# Sensors.net
KiCad netlist of a schematic drawn in Altium Designer
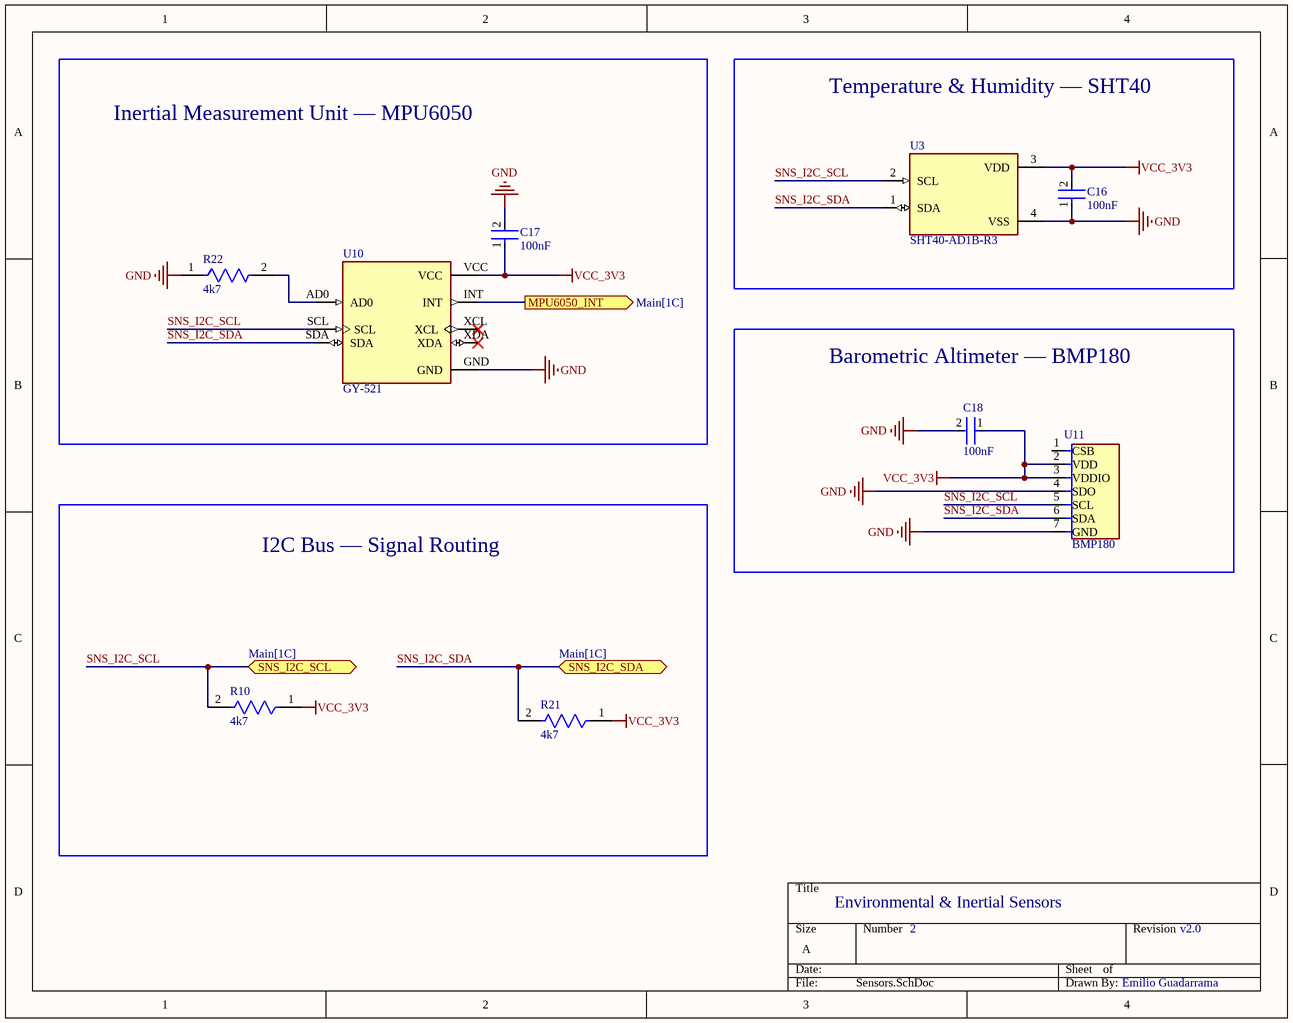
[diagram p0: Sensors.SchDoc]

(export (version "E")
  (design (tool "Eeschema 10.0.6"))
  (components
    (comp (ref "C16")
      (value "100nF")
      (footprint "FP-C0805C-DN-MFG")
      (description "CAP CER 0.1UF 50V X7R 0805")
      (fields
        (field (name "MANUFACTURER PART NUMBER") "C0805C104K5RACTU")
        (field (name "MANUFACTURER") "KEMET")
      )
      (libsource (lib "Altium Content Vault") (part "b4654b650e69147ec39a6b967a45e02"))
    )
    (comp (ref "C17")
      (value "100nF")
      (footprint "FP-C0805C-DN-MFG")
      (description "CAP CER 0.1UF 50V X7R 0805")
      (fields
        (field (name "MANUFACTURER PART NUMBER") "C0805C104K5RACTU")
        (field (name "MANUFACTURER") "KEMET")
      )
      (libsource (lib "Altium Content Vault") (part "b4654b650e69147ec39a6b967a45e02"))
    )
    (comp (ref "C18")
      (value "100nF")
      (footprint "FP-C0805C-DN-MFG")
      (description "CAP CER 0.1UF 50V X7R 0805")
      (fields
        (field (name "MANUFACTURER PART NUMBER") "C0805C104K5RACTU")
        (field (name "MANUFACTURER") "KEMET")
      )
      (libsource (lib "Altium Content Vault") (part "b4654b650e69147ec39a6b967a45e02"))
    )
    (comp (ref "R10")
      (value "4k7")
      (footprint "FP-MCT0603-IPC_A")
      (description "RES SMD 100 OHM 1% 1/8W 0603")
      (fields (field (name "TOLERANCE") "0.1%"))
      (libsource (lib "Altium Content Vault") (part "1029c3af85768c4190bb7ad29bc67b5"))
    )
    (comp (ref "R21")
      (value "4k7")
      (footprint "FP-MCT0603-IPC_A")
      (description "RES SMD 100 OHM 1% 1/8W 0603")
      (fields (field (name "TOLERANCE") "0.1%"))
      (libsource (lib "Altium Content Vault") (part "1029c3af85768c4190bb7ad29bc67b5"))
    )
    (comp (ref "R22")
      (value "4k7")
      (footprint "FP-MCT0603-IPC_A")
      (description "RES SMD 100 OHM 1% 1/8W 0603")
      (fields (field (name "TOLERANCE") "0.1%"))
      (libsource (lib "Altium Content Vault") (part "1029c3af85768c4190bb7ad29bc67b5"))
    )
    (comp (ref "U3")
      (value "SHT40-AD1B-R3")
      (footprint "SHT4X")
      (fields (field (name "MF") "Sensirion"))
      (libsource (lib "HumTemp-SHT40-AD1B-R3") (part "SHT40-AD1B-R3"))
    )
    (comp (ref "U10")
      (value "GY-521")
      (footprint "MODULE_GY-521")
      (description "Triple Axis Accelerometer Gyro Breakout")
      (fields (field (name "MF") "GODREAM FORDREAM CO., LIMITED"))
      (libsource (lib "GY-521_IMU_with_MountingHoles") (part "GY-521"))
    )
    (comp (ref "U11")
      (value "BMP180")
      (footprint "LGA7-1.5-3.8X3.6MM")
      (description "Pressure Sensor 4.35PSI ~ 15.95PSI (30kPa ~ 110kPa) Absolute - 16 ~ 19 b 7-VLGA")
      (fields (field (name "MF") "Bosch"))
      (libsource (lib "BMP180") (part "PRESSURE-BMP180(LGA7)"))
    )
  )
  (nets
    (net (code "1") (name "/MPU6050_INT") (class "Default")
      (node (ref "U10") (pin "INT") (pinfunction "INT_INT") (pintype "output"))
    )
    (net (code "2") (name "/SNS_I2C_SCL") (class "Default")
      (node (ref "R10") (pin "2") (pinfunction "2_2") (pintype "passive"))
      (node (ref "U10") (pin "SCL") (pinfunction "SCL_SCL") (pintype "input"))
      (node (ref "U11") (pin "5") (pinfunction "SCL_5") (pintype "bidirectional"))
      (node (ref "U3") (pin "2") (pinfunction "SCL_2") (pintype "input"))
    )
    (net (code "3") (name "/SNS_I2C_SDA") (class "Default")
      (node (ref "R21") (pin "2") (pinfunction "2_2") (pintype "passive"))
      (node (ref "U10") (pin "SDA") (pinfunction "SDA_SDA") (pintype "bidirectional"))
      (node (ref "U11") (pin "6") (pinfunction "SDA_6") (pintype "bidirectional"))
      (node (ref "U3") (pin "1") (pinfunction "SDA_1") (pintype "bidirectional"))
    )
    (net (code "4") (name "GND") (class "Default")
      (node (ref "C16") (pin "1") (pinfunction "1_1") (pintype "passive"))
      (node (ref "C17") (pin "2") (pinfunction "2_2") (pintype "passive"))
      (node (ref "C18") (pin "2") (pinfunction "2_2") (pintype "passive"))
      (node (ref "R22") (pin "1") (pinfunction "1_1") (pintype "passive"))
      (node (ref "U10") (pin "GND") (pinfunction "GND_GND") (pintype "power_in"))
      (node (ref "U11") (pin "4") (pinfunction "SDO_4") (pintype "bidirectional"))
      (node (ref "U11") (pin "7") (pinfunction "GND_7") (pintype "bidirectional"))
      (node (ref "U3") (pin "4") (pinfunction "VSS_4") (pintype "power_in"))
    )
    (net (code "5") (name "Net-(R22-Pad2)") (class "Default")
      (node (ref "R22") (pin "2") (pinfunction "2_2") (pintype "passive"))
      (node (ref "U10") (pin "AD0") (pinfunction "AD0_AD0") (pintype "input"))
    )
    (net (code "6") (name "VCC_3V3") (class "Default")
      (node (ref "C16") (pin "2") (pinfunction "2_2") (pintype "passive"))
      (node (ref "C17") (pin "1") (pinfunction "1_1") (pintype "passive"))
      (node (ref "C18") (pin "1") (pinfunction "1_1") (pintype "passive"))
      (node (ref "R10") (pin "1") (pinfunction "1_1") (pintype "passive"))
      (node (ref "R21") (pin "1") (pinfunction "1_1") (pintype "passive"))
      (node (ref "U10") (pin "VCC") (pinfunction "VCC_VCC") (pintype "power_in"))
      (node (ref "U11") (pin "2") (pinfunction "VDD_2") (pintype "bidirectional"))
      (node (ref "U11") (pin "3") (pinfunction "VDDIO_3") (pintype "bidirectional"))
      (node (ref "U3") (pin "3") (pinfunction "VDD_3") (pintype "power_in"))
    )
    (net (code "7") (name "unconnected-(U10-PadXCL)") (class "Default")
      (node (ref "U10") (pin "XCL") (pinfunction "XCL_XCL") (pintype "output+no_connect"))
    )
    (net (code "8") (name "unconnected-(U10-PadXDA)") (class "Default")
      (node (ref "U10") (pin "XDA") (pinfunction "XDA_XDA") (pintype "bidirectional+no_connect"))
    )
    (net (code "9") (name "unconnected-(U11-CSB-Pad1)") (class "Default")
      (node (ref "U11") (pin "1") (pinfunction "CSB_1") (pintype "bidirectional"))
    )
  )
)
